# Actuator.net
KiCad netlist of a schematic drawn in Altium Designer
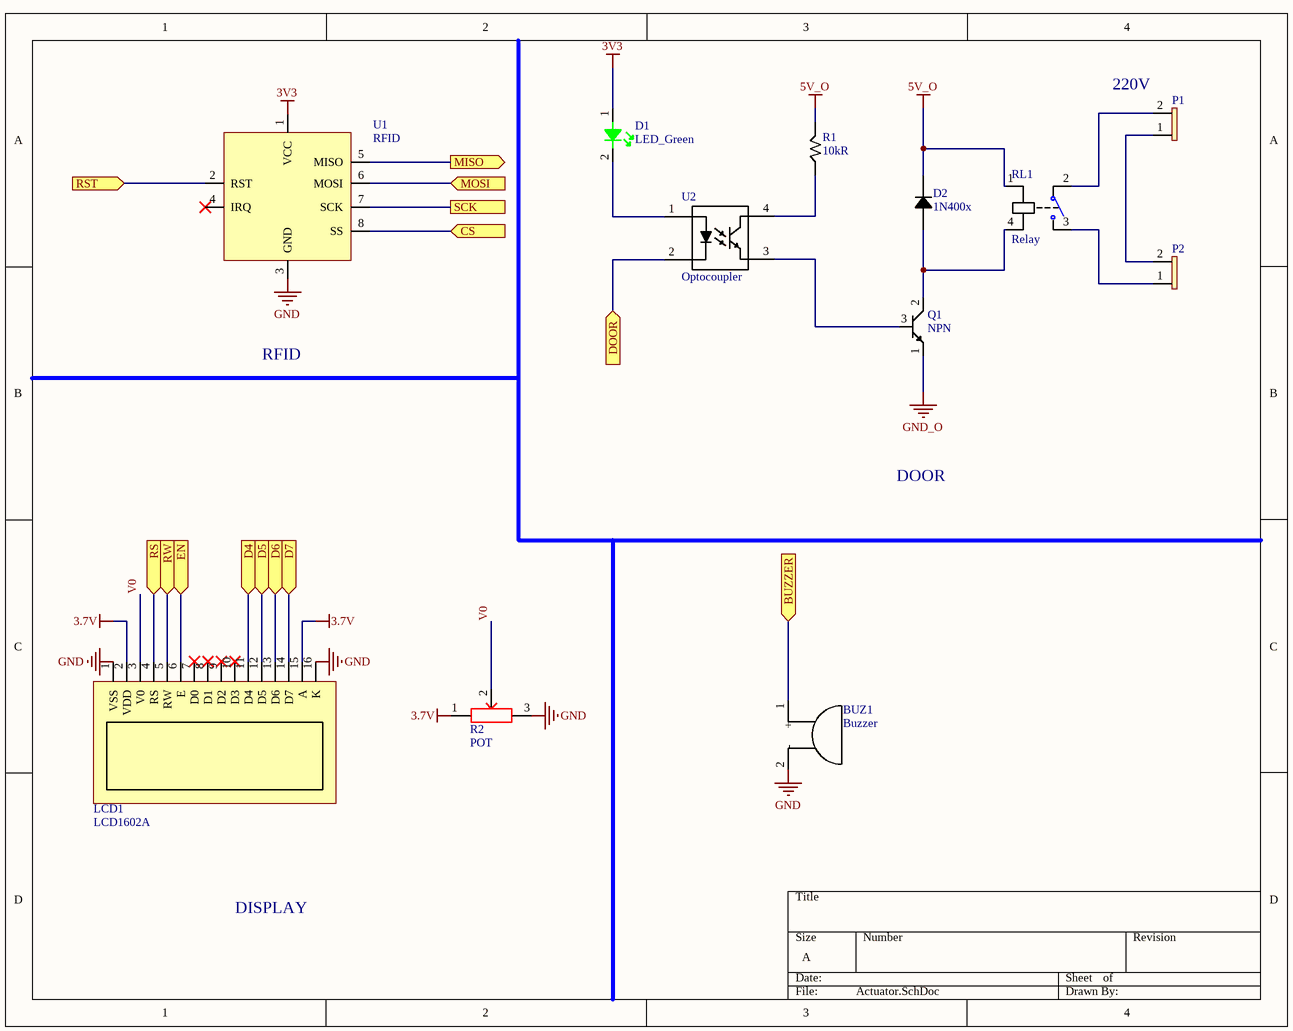
[diagram p0: Actuator.SchDoc]

(export (version "E")
  (design (tool "Eeschema 10.0.6"))
  (components
    (comp (ref "BUZ1")
      (value "Buzzer")
      (footprint "Buzzer_7.6")
      (libsource (lib "Altium Lib") (part "Buzzer"))
    )
    (comp (ref "D1")
      (value "LED_Green")
      (footprint "LED SMD 0805")
      (libsource (lib "Altium Lib") (part "LED_Green"))
    )
    (comp (ref "D2")
      (value "1N400x")
      (footprint "1N4007-M7")
      (description "1A - 1kV")
      (libsource (lib "Altium Lib") (part "Diode 1N4007"))
    )
    (comp (ref "LCD1")
      (value "LCD1602A")
      (footprint "Altium Lib:LCD1602A")
      (libsource (lib "Altium Lib") (part "LCD1602A"))
    )
    (comp (ref "P1")
      (value "Header 1*2 Pins")
      (footprint "HDR_M_2_PINS_2.54")
      (libsource (lib "Altium Lib") (part "Header 1x2 Pins"))
    )
    (comp (ref "P2")
      (value "Header 1*2 Pins")
      (footprint "HDR_M_2_PINS_2.54")
      (libsource (lib "Altium Lib") (part "Header 1x2 Pins"))
    )
    (comp (ref "Q1")
      (value "NPN")
      (footprint "to-92")
      (description "Transistor NPN")
      (libsource (lib "Altium Lib") (part "2SC1815"))
    )
    (comp (ref "R1")
      (value "10kR")
      (footprint "Altium Lib:RESC0805")
      (description "Resistor_TH_1/4W")
      (libsource (lib "Altium Lib") (part "Resistor"))
    )
    (comp (ref "R2")
      (value "POT")
      (footprint "Altium Lib:WH148-3P")
      (libsource (lib "Altium Lib") (part "POT_3Pins"))
    )
    (comp (ref "RL1")
      (value "Relay")
      (footprint "Relay G5NB")
      (description "4 Pins")
      (libsource (lib "Altium Lib") (part "Relay G5NB"))
    )
    (comp (ref "U1")
      (value "RFID")
      (footprint "RFID RC 522 Module")
      (libsource (lib "Altium Lib") (part "RFID RC522 Module"))
    )
    (comp (ref "U2")
      (value "Optocoupler")
      (footprint "DIP 4")
      (description "Opto")
      (libsource (lib "Altium Lib") (part "Optocoupler"))
    )
  )
  (nets
    (net (code "1") (name "/BUZZER") (class "Default")
      (node (ref "BUZ1") (pin "1") (pinfunction "+_1") (pintype "passive"))
    )
    (net (code "2") (name "/CS") (class "Default")
      (node (ref "U1") (pin "8") (pinfunction "SS_8") (pintype "passive"))
    )
    (net (code "3") (name "/D4") (class "Default")
      (node (ref "LCD1") (pin "11") (pinfunction "D4_11") (pintype "passive"))
    )
    (net (code "4") (name "/D5") (class "Default")
      (node (ref "LCD1") (pin "12") (pinfunction "D5_12") (pintype "passive"))
    )
    (net (code "5") (name "/D6") (class "Default")
      (node (ref "LCD1") (pin "13") (pinfunction "D6_13") (pintype "passive"))
    )
    (net (code "6") (name "/D7") (class "Default")
      (node (ref "LCD1") (pin "14") (pinfunction "D7_14") (pintype "passive"))
    )
    (net (code "7") (name "/DOOR") (class "Default")
      (node (ref "U2") (pin "2") (pinfunction "Cathode_2") (pintype "passive"))
    )
    (net (code "8") (name "/EN") (class "Default")
      (node (ref "LCD1") (pin "6") (pinfunction "E_6") (pintype "passive"))
    )
    (net (code "9") (name "/MISO") (class "Default")
      (node (ref "U1") (pin "5") (pinfunction "MISO_5") (pintype "passive"))
    )
    (net (code "10") (name "/MOSI") (class "Default")
      (node (ref "U1") (pin "6") (pinfunction "MOSI_6") (pintype "passive"))
    )
    (net (code "11") (name "/RS") (class "Default")
      (node (ref "LCD1") (pin "4") (pinfunction "RS_4") (pintype "passive"))
    )
    (net (code "12") (name "/RST") (class "Default")
      (node (ref "U1") (pin "2") (pinfunction "RST_2") (pintype "passive"))
    )
    (net (code "13") (name "/RW") (class "Default")
      (node (ref "LCD1") (pin "5") (pinfunction "RW_5") (pintype "passive"))
    )
    (net (code "14") (name "/SCK") (class "Default")
      (node (ref "U1") (pin "7") (pinfunction "SCK_7") (pintype "passive"))
    )
    (net (code "15") (name "/V0") (class "Default")
      (node (ref "LCD1") (pin "3") (pinfunction "V0_3") (pintype "passive"))
      (node (ref "R2") (pin "2") (pinfunction "2_2") (pintype "passive"))
    )
    (net (code "16") (name "3.7V") (class "Default")
      (node (ref "LCD1") (pin "15") (pinfunction "A_15") (pintype "passive"))
      (node (ref "LCD1") (pin "2") (pinfunction "VDD_2") (pintype "passive"))
      (node (ref "R2") (pin "1") (pinfunction "1_1") (pintype "passive"))
    )
    (net (code "17") (name "3V3") (class "Default")
      (node (ref "D1") (pin "1") (pinfunction "1_1") (pintype "passive"))
      (node (ref "U1") (pin "1") (pinfunction "VCC_1") (pintype "passive"))
    )
    (net (code "18") (name "5V_O") (class "Default")
      (node (ref "D2") (pin "2") (pinfunction "2_2") (pintype "passive"))
      (node (ref "R1") (pin "2") (pinfunction "2_2") (pintype "passive"))
      (node (ref "RL1") (pin "1") (pinfunction "1_1") (pintype "passive"))
    )
    (net (code "19") (name "GND") (class "Default")
      (node (ref "BUZ1") (pin "2") (pinfunction "-_2") (pintype "passive"))
      (node (ref "LCD1") (pin "1") (pinfunction "VSS_1") (pintype "passive"))
      (node (ref "LCD1") (pin "16") (pinfunction "K_16") (pintype "passive"))
      (node (ref "R2") (pin "3") (pinfunction "3_3") (pintype "passive"))
      (node (ref "U1") (pin "3") (pinfunction "GND_3") (pintype "passive"))
    )
    (net (code "20") (name "GND_O") (class "Default")
      (node (ref "Q1") (pin "1") (pinfunction "Emitter_1") (pintype "passive"))
    )
    (net (code "21") (name "Net-(P1-Pad1)") (class "Default")
      (node (ref "P1") (pin "1") (pinfunction "1_1") (pintype "passive"))
      (node (ref "P2") (pin "2") (pinfunction "2_2") (pintype "passive"))
    )
    (net (code "22") (name "Net-(P1-Pad2)") (class "Default")
      (node (ref "P1") (pin "2") (pinfunction "2_2") (pintype "passive"))
      (node (ref "RL1") (pin "2") (pinfunction "2_2") (pintype "passive"))
    )
    (net (code "23") (name "Net-(P2-Pad1)") (class "Default")
      (node (ref "P2") (pin "1") (pinfunction "1_1") (pintype "passive"))
      (node (ref "RL1") (pin "3") (pinfunction "3_3") (pintype "passive"))
    )
    (net (code "24") (name "Net-(Q1-Base)") (class "Default")
      (node (ref "Q1") (pin "3") (pinfunction "Base_3") (pintype "passive"))
      (node (ref "U2") (pin "3") (pinfunction "Emitter_3") (pintype "passive"))
    )
    (net (code "25") (name "Net-(Q1-Collector)") (class "Default")
      (node (ref "D2") (pin "1") (pinfunction "1_1") (pintype "passive"))
      (node (ref "Q1") (pin "2") (pinfunction "Collector_2") (pintype "passive"))
      (node (ref "RL1") (pin "4") (pinfunction "4_4") (pintype "passive"))
    )
    (net (code "26") (name "Net-(U2-Anode)") (class "Default")
      (node (ref "D1") (pin "2") (pinfunction "2_2") (pintype "passive"))
      (node (ref "U2") (pin "1") (pinfunction "Anode_1") (pintype "passive"))
    )
    (net (code "27") (name "Net-(U2-Collector)") (class "Default")
      (node (ref "R1") (pin "1") (pinfunction "1_1") (pintype "passive"))
      (node (ref "U2") (pin "4") (pinfunction "Collector_4") (pintype "passive"))
    )
    (net (code "28") (name "unconnected-(LCD1-D0-Pad7)") (class "Default")
      (node (ref "LCD1") (pin "7") (pinfunction "D0_7") (pintype "passive+no_connect"))
    )
    (net (code "29") (name "unconnected-(LCD1-D1-Pad8)") (class "Default")
      (node (ref "LCD1") (pin "8") (pinfunction "D1_8") (pintype "passive+no_connect"))
    )
    (net (code "30") (name "unconnected-(LCD1-D2-Pad9)") (class "Default")
      (node (ref "LCD1") (pin "9") (pinfunction "D2_9") (pintype "passive+no_connect"))
    )
    (net (code "31") (name "unconnected-(LCD1-D3-Pad10)") (class "Default")
      (node (ref "LCD1") (pin "10") (pinfunction "D3_10") (pintype "passive+no_connect"))
    )
    (net (code "32") (name "unconnected-(U1-IRQ-Pad4)") (class "Default")
      (node (ref "U1") (pin "4") (pinfunction "IRQ_4") (pintype "passive+no_connect"))
    )
  )
)
